# DSO_Power.net
KiCad netlist of a schematic drawn in Altium Designer
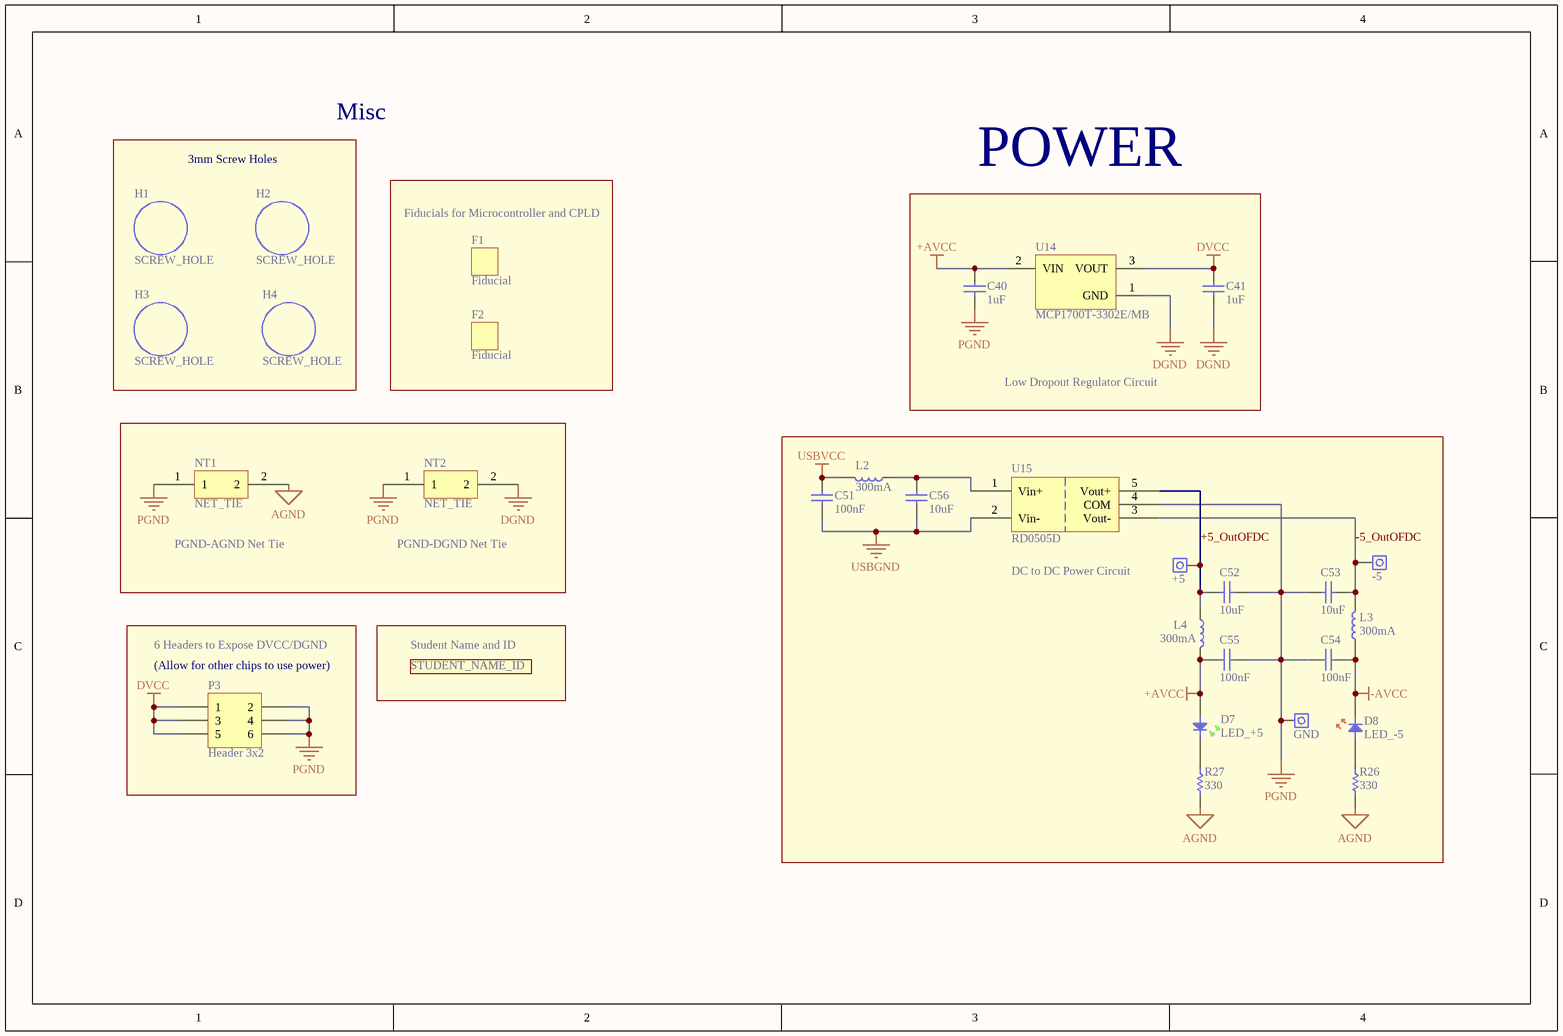
[diagram p0: DSO_Power.SchDoc]

(export (version "E")
  (design (tool "Eeschema 10.0.6"))
  (components
    (comp (ref "C40")
      (value "1uF")
      (footprint "0805C")
      (description "Capacitor")
      (fields (field (name "REVIEWED BY") "RM - 2018/08/05"))
      (libsource (lib "DSO") (part "C"))
    )
    (comp (ref "C41")
      (value "1uF")
      (footprint "0805C")
      (description "Capacitor")
      (fields (field (name "REVIEWED BY") "RM - 2018/08/05"))
      (libsource (lib "DSO") (part "C"))
    )
    (comp (ref "C51")
      (value "100nF")
      (footprint "0805C")
      (description "Capacitor")
      (fields (field (name "REVIEWED BY") "RM - 2018/08/05"))
      (libsource (lib "DSO") (part "C"))
    )
    (comp (ref "C52")
      (value "10uF")
      (footprint "0805C")
      (description "Capacitor")
      (fields (field (name "REVIEWED BY") "RM - 2018/08/05"))
      (libsource (lib "DSO") (part "C"))
    )
    (comp (ref "C53")
      (value "10uF")
      (footprint "0805C")
      (description "Capacitor")
      (fields (field (name "REVIEWED BY") "RM - 2018/08/05"))
      (libsource (lib "DSO") (part "C"))
    )
    (comp (ref "C54")
      (value "100nF")
      (footprint "0805C")
      (description "Capacitor")
      (fields (field (name "REVIEWED BY") "RM - 2018/08/05"))
      (libsource (lib "DSO") (part "C"))
    )
    (comp (ref "C55")
      (value "100nF")
      (footprint "0805C")
      (description "Capacitor")
      (fields (field (name "REVIEWED BY") "RM - 2018/08/05"))
      (libsource (lib "DSO") (part "C"))
    )
    (comp (ref "C56")
      (value "10uF")
      (footprint "0805C")
      (description "Capacitor")
      (fields (field (name "REVIEWED BY") "RM - 2018/08/05"))
      (libsource (lib "DSO") (part "C"))
    )
    (comp (ref "D7")
      (value "LED_+5")
      (footprint "0805D-GREEN")
      (description "Light Emitting Diode")
      (fields (field (name "REVIEWED BY") "RM - 2018/08/05"))
      (libsource (lib "DSO") (part "LED GREEN"))
    )
    (comp (ref "D8")
      (value "LED_-5")
      (footprint "0805D-RED")
      (description "Light Emitting Diode")
      (fields (field (name "REVIEWED BY") "RM - 2018/08/05"))
      (libsource (lib "DSO") (part "LED RED"))
    )
    (comp (ref "F1") (value "Fiducial") (footprint "Fiducial") (libsource (lib "DSO") (part "Fiducial")))
    (comp (ref "F2") (value "Fiducial") (footprint "Fiducial") (libsource (lib "DSO") (part "Fiducial")))
    (comp (ref "H1")
      (value "SCREW_HOLE")
      (footprint "SCREW_HOLE")
      (libsource (lib "DSO") (part "SCREW_HOLE"))
    )
    (comp (ref "H2")
      (value "SCREW_HOLE")
      (footprint "SCREW_HOLE")
      (libsource (lib "DSO") (part "SCREW_HOLE"))
    )
    (comp (ref "H3")
      (value "SCREW_HOLE")
      (footprint "SCREW_HOLE")
      (libsource (lib "DSO") (part "SCREW_HOLE"))
    )
    (comp (ref "H4")
      (value "SCREW_HOLE")
      (footprint "SCREW_HOLE")
      (libsource (lib "DSO") (part "SCREW_HOLE"))
    )
    (comp (ref "L2")
      (value "300mA")
      (footprint "0805")
      (description "Inductor")
      (fields (field (name "REVIEWED BY") "RM - 2018/08/05"))
      (libsource (lib "DSO") (part "I"))
    )
    (comp (ref "L3")
      (value "300mA")
      (footprint "0805")
      (description "Inductor")
      (fields (field (name "REVIEWED BY") "RM - 2018/08/05"))
      (libsource (lib "DSO") (part "I"))
    )
    (comp (ref "L4")
      (value "300mA")
      (footprint "0805")
      (description "Inductor")
      (fields (field (name "REVIEWED BY") "RM - 2018/08/05"))
      (libsource (lib "DSO") (part "I"))
    )
    (comp (ref "Name*")
      (value "NAME")
      (footprint "NAME")
      (description "Student Name and ID")
      (libsource (lib "DSO") (part "NAME"))
    )
    (comp (ref "NT1")
      (value "NET_TIE")
      (footprint "NET_TIE")
      (description "Net Tie")
      (libsource (lib "DSO") (part "NET_TIE"))
    )
    (comp (ref "NT2")
      (value "NET_TIE")
      (footprint "NET_TIE")
      (description "Net Tie")
      (libsource (lib "DSO") (part "NET_TIE"))
    )
    (comp (ref "P3")
      (value "Header 3x2")
      (footprint "HDR3x2")
      (description "Header, 5-Pin")
      (fields (field (name "REVIEWED BY") "RM - 2018/08/05"))
      (libsource (lib "DSO") (part "Header 3x2"))
    )
    (comp (ref "R26")
      (value "330")
      (footprint "0805")
      (description "Resistor")
      (fields (field (name "REVIEWED BY") "RM - 2018/08/05"))
      (libsource (lib "DSO") (part "R"))
    )
    (comp (ref "R27")
      (value "330")
      (footprint "0805")
      (description "Resistor")
      (fields (field (name "REVIEWED BY") "RM - 2018/08/05"))
      (libsource (lib "DSO") (part "R"))
    )
    (comp (ref "TP9")
      (value "-5")
      (footprint "PIN 1.8mm")
      (description "Pad")
      (libsource (lib "DSO") (part "WIRE"))
    )
    (comp (ref "TP10")
      (value "GND")
      (footprint "PIN 1.8mm")
      (description "Pad")
      (libsource (lib "DSO") (part "WIRE"))
    )
    (comp (ref "TP11")
      (value "+5")
      (footprint "PIN 1.8mm")
      (description "Pad")
      (libsource (lib "DSO") (part "WIRE"))
    )
    (comp (ref "U14")
      (value "MCP1700T-3302E/MB")
      (footprint "SOT89")
      (description "Low Quiescent Current LDO, 3-Pin SOT-89, Extended Temperature, Tape and Reel")
      (fields (field (name "REVIEWED BY") "RM - 2018/08/05"))
      (libsource (lib "DSO") (part "MCP1700T"))
    )
    (comp (ref "U15")
      (value "RD0505D")
      (footprint "SIP_NMG")
      (description "(ADV) DC to DC converter 5V in +-5V out")
      (fields (field (name "REVIEWED BY") "RM - 2018/08/05"))
      (libsource (lib "DSO") (part "RD0505D"))
    )
  )
  (nets
    (net (code "1") (name "+AVCC") (class "Default")
      (node (ref "C40") (pin "1") (pinfunction "1_1") (pintype "passive"))
      (node (ref "C55") (pin "1") (pinfunction "1_1") (pintype "passive"))
      (node (ref "D7") (pin "A") (pinfunction "A_A") (pintype "passive"))
      (node (ref "L4") (pin "2") (pinfunction "2_2") (pintype "passive"))
      (node (ref "U14") (pin "2") (pinfunction "VIN_2") (pintype "power_in"))
    )
    (net (code "2") (name "-AVCC") (class "Default")
      (node (ref "C54") (pin "1") (pinfunction "1_1") (pintype "passive"))
      (node (ref "D8") (pin "K") (pinfunction "K_K") (pintype "passive"))
      (node (ref "L3") (pin "1") (pinfunction "1_1") (pintype "passive"))
    )
    (net (code "3") (name "/+5_OutOFDC") (class "Default")
      (node (ref "C52") (pin "1") (pinfunction "1_1") (pintype "passive"))
      (node (ref "L4") (pin "1") (pinfunction "1_1") (pintype "passive"))
      (node (ref "TP11") (pin "1") (pintype "passive"))
      (node (ref "U15") (pin "5") (pinfunction "Vout+_5") (pintype "passive"))
    )
    (net (code "4") (name "/-5_OutOFDC") (class "Default")
      (node (ref "C53") (pin "1") (pinfunction "1_1") (pintype "passive"))
      (node (ref "L3") (pin "2") (pinfunction "2_2") (pintype "passive"))
      (node (ref "TP9") (pin "1") (pintype "passive"))
      (node (ref "U15") (pin "3") (pinfunction "Vout-_3") (pintype "passive"))
    )
    (net (code "5") (name "AGND") (class "Default")
      (node (ref "NT1") (pin "2") (pinfunction "2_2") (pintype "passive"))
      (node (ref "R26") (pin "2") (pintype "passive"))
      (node (ref "R27") (pin "2") (pintype "passive"))
    )
    (net (code "6") (name "DGND") (class "Default")
      (node (ref "C41") (pin "2") (pinfunction "2_2") (pintype "passive"))
      (node (ref "NT2") (pin "2") (pinfunction "2_2") (pintype "passive"))
      (node (ref "U14") (pin "1") (pinfunction "GND_1") (pintype "power_in"))
    )
    (net (code "7") (name "DVCC") (class "Default")
      (node (ref "C41") (pin "1") (pinfunction "1_1") (pintype "passive"))
      (node (ref "P3") (pin "1") (pinfunction "1_1") (pintype "passive"))
      (node (ref "P3") (pin "3") (pinfunction "3_3") (pintype "passive"))
      (node (ref "P3") (pin "5") (pinfunction "5_5") (pintype "passive"))
      (node (ref "U14") (pin "3") (pinfunction "VOUT_3") (pintype "power_in"))
    )
    (net (code "8") (name "Net-(D7-PadK)") (class "Default")
      (node (ref "D7") (pin "K") (pinfunction "K_K") (pintype "passive"))
      (node (ref "R27") (pin "1") (pintype "passive"))
    )
    (net (code "9") (name "Net-(D8-PadA)") (class "Default")
      (node (ref "D8") (pin "A") (pinfunction "A_A") (pintype "passive"))
      (node (ref "R26") (pin "1") (pintype "passive"))
    )
    (net (code "10") (name "Net-(U15-Vin+)") (class "Default")
      (node (ref "C56") (pin "1") (pinfunction "1_1") (pintype "passive"))
      (node (ref "L2") (pin "1") (pinfunction "1_1") (pintype "passive"))
      (node (ref "U15") (pin "1") (pinfunction "Vin+_1") (pintype "passive"))
    )
    (net (code "11") (name "PGND") (class "Default")
      (node (ref "C40") (pin "2") (pinfunction "2_2") (pintype "passive"))
      (node (ref "C52") (pin "2") (pinfunction "2_2") (pintype "passive"))
      (node (ref "C53") (pin "2") (pinfunction "2_2") (pintype "passive"))
      (node (ref "C54") (pin "2") (pinfunction "2_2") (pintype "passive"))
      (node (ref "C55") (pin "2") (pinfunction "2_2") (pintype "passive"))
      (node (ref "NT1") (pin "1") (pinfunction "1_1") (pintype "passive"))
      (node (ref "NT2") (pin "1") (pinfunction "1_1") (pintype "passive"))
      (node (ref "P3") (pin "2") (pinfunction "2_2") (pintype "passive"))
      (node (ref "P3") (pin "4") (pinfunction "4_4") (pintype "passive"))
      (node (ref "P3") (pin "6") (pinfunction "6_6") (pintype "passive"))
      (node (ref "TP10") (pin "1") (pintype "passive"))
      (node (ref "U15") (pin "4") (pinfunction "COM_4") (pintype "passive"))
    )
    (net (code "12") (name "USBGND") (class "Default")
      (node (ref "C51") (pin "2") (pinfunction "2_2") (pintype "passive"))
      (node (ref "C56") (pin "2") (pinfunction "2_2") (pintype "passive"))
      (node (ref "U15") (pin "2") (pinfunction "Vin-_2") (pintype "passive"))
    )
    (net (code "13") (name "USBVCC") (class "Default")
      (node (ref "C51") (pin "1") (pinfunction "1_1") (pintype "passive"))
      (node (ref "L2") (pin "2") (pinfunction "2_2") (pintype "passive"))
    )
  )
)
